# power.net
KiCad netlist of a schematic drawn in Altium Designer
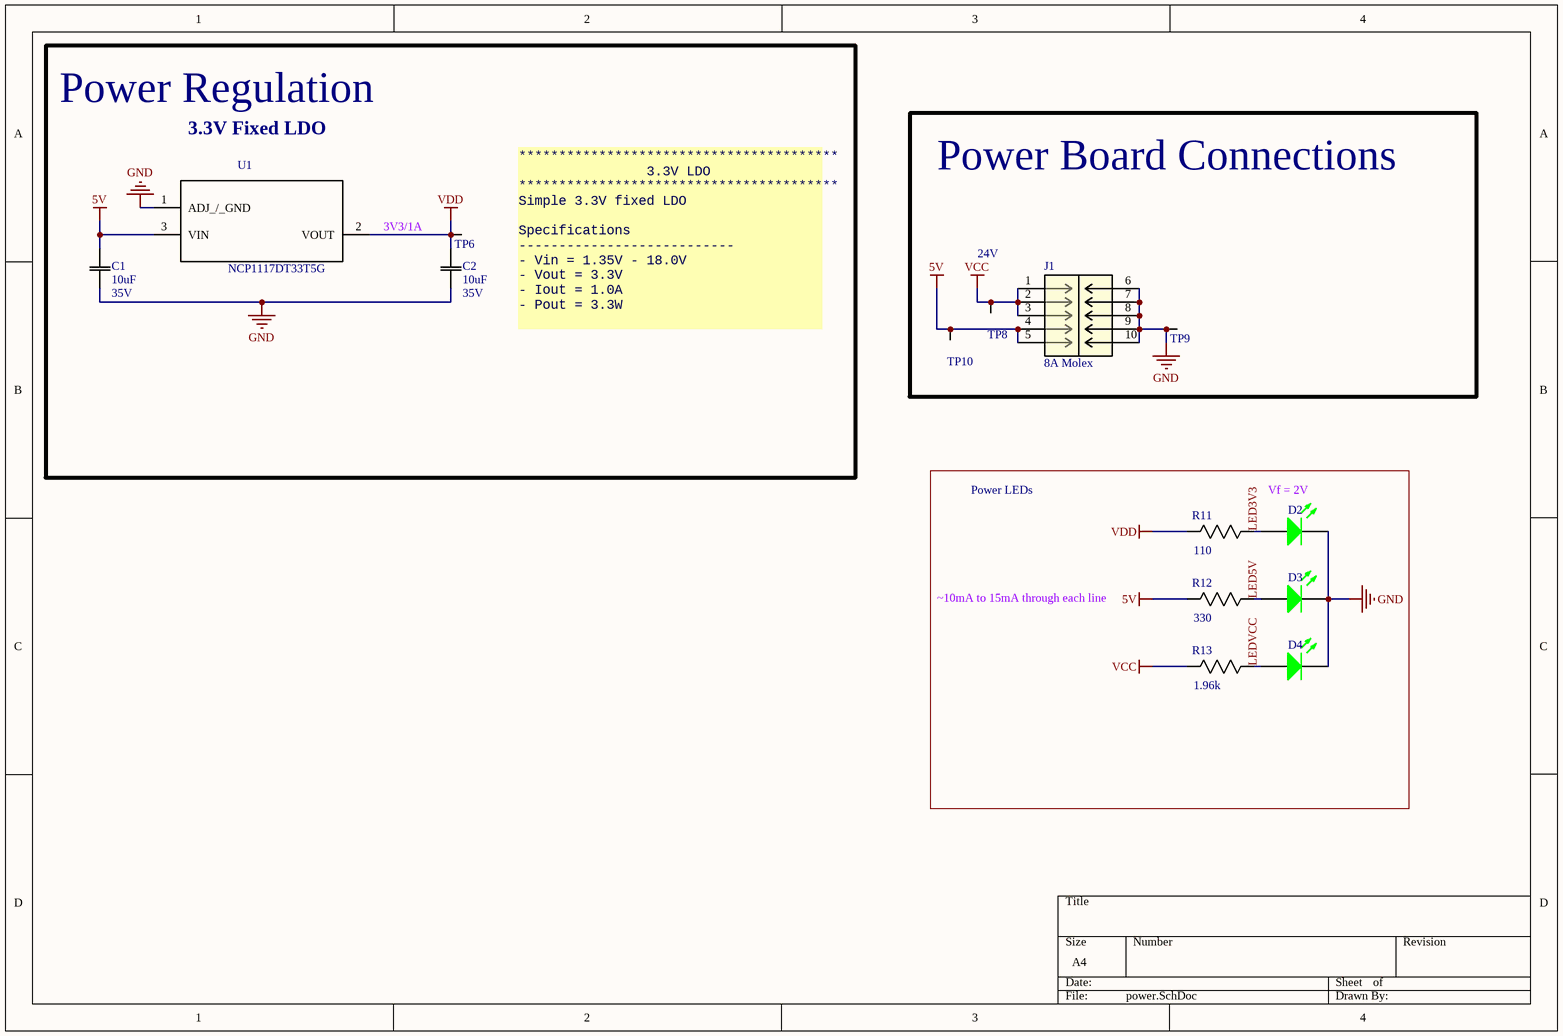
[diagram p0: power.SchDoc]

(export (version "E")
  (design (tool "Eeschema 10.0.6"))
  (components
    (comp (ref "C1")
      (value "10uF")
      (footprint "0805")
      (description "Default Symbol for Capacitors")
      (fields
        (field (name "TOLERANCE") "10%")
        (field (name "RATING") "35V")
        (field (name "PART NUMBER") "CAP 10uF 35V_1")
      )
      (libsource (lib "capacitor_library") (part "CAP_Default"))
    )
    (comp (ref "C2")
      (value "10uF")
      (footprint "0805")
      (description "Default Symbol for Capacitors")
      (fields
        (field (name "TOLERANCE") "10%")
        (field (name "RATING") "35V")
        (field (name "PART NUMBER") "CAP 10uF 35V_1")
      )
      (libsource (lib "capacitor_library") (part "CAP_Default"))
    )
    (comp (ref "D2")
      (value "0603 2V")
      (footprint "0603 - LED")
      (description "LED Uni-Color Green 574nm 2-Pin Chip LED T/R")
      (fields (field (name "PART NUMBER") "LED GREEN SMD 0603"))
      (libsource (lib "Diode_Library") (part "LED GREEN SMD 0603"))
    )
    (comp (ref "D3")
      (value "0603 2V")
      (footprint "0603 - LED")
      (description "LED Uni-Color Green 574nm 2-Pin Chip LED T/R")
      (fields (field (name "PART NUMBER") "LED GREEN SMD 0603"))
      (libsource (lib "Diode_Library") (part "LED GREEN SMD 0603"))
    )
    (comp (ref "D4")
      (value "0603 2V")
      (footprint "0603 - LED")
      (description "LED Uni-Color Green 574nm 2-Pin Chip LED T/R")
      (fields (field (name "PART NUMBER") "LED GREEN SMD 0603"))
      (libsource (lib "Diode_Library") (part "LED GREEN SMD 0603"))
    )
    (comp (ref "J1")
      (value "8A Molex")
      (footprint "MOLEX_0430451012")
      (description "CONN HEADER VERT 10POS 3MM")
      (fields (field (name "PART NUMBER") "CN HDR 10POS MOLEX 0430451012"))
      (libsource (lib "Connector_Library") (part "CN HDR 10POS MOLEX 0430451012"))
    )
    (comp (ref "R11")
      (value "110")
      (footprint "0603")
      (description "Default Resistor Symbol")
      (fields (field (name "TOLERANCE") "1%") (field (name "PART NUMBER") "RES 110.0 1/8W - 1%"))
      (libsource (lib "") (part "RES_DEFAULT_1"))
    )
    (comp (ref "R12")
      (value "330")
      (footprint "0603")
      (description "Default Resistor Symbol")
      (fields (field (name "TOLERANCE") "5%") (field (name "PART NUMBER") "RES 330.0 1/8W - 5%"))
      (libsource (lib "Resistor_Library") (part "RES_DEFAULT"))
    )
    (comp (ref "R13")
      (value "1.96k")
      (footprint "0603")
      (description "Default Resistor Symbol")
      (fields (field (name "TOLERANCE") "1%") (field (name "PART NUMBER") "RES 1.96k 1/8W"))
      (libsource (lib "Resistor_Library") (part "RES_DEFAULT"))
    )
    (comp (ref "TP6")
      (value "VDD")
      (footprint "TP")
      (fields (field (name "PART NUMBER") "Test Point (Via)"))
      (libsource (lib "IC_Library") (part "Test Point (Via)"))
    )
    (comp (ref "TP8")
      (value "VCC")
      (footprint "TP")
      (fields (field (name "PART NUMBER") "Test Point (Via)"))
      (libsource (lib "IC_Library") (part "Test Point (Via)"))
    )
    (comp (ref "TP9")
      (value "GND")
      (footprint "TP")
      (fields (field (name "PART NUMBER") "Test Point (Via)"))
      (libsource (lib "IC_Library") (part "Test Point (Via)"))
    )
    (comp (ref "TP10")
      (value "5V")
      (footprint "TP")
      (fields (field (name "PART NUMBER") "Test Point (Via)"))
      (libsource (lib "IC_Library") (part "Test Point (Via)"))
    )
    (comp (ref "U1")
      (value "NCP1117DT33T5G")
      (footprint "DPAK (TO-252)")
      (description "Linear Voltage Regulator IC Positive Fixed 1 Output 1A DPAK")
      (libsource (lib "IC_Library") (part "NCP1117DT33T5G"))
    )
  )
  (nets
    (net (code "1") (name "/LED3V3") (class "Default")
      (node (ref "D2") (pin "1") (pinfunction "A_1") (pintype "passive"))
      (node (ref "R11") (pin "1") (pinfunction "R1_1") (pintype "passive"))
    )
    (net (code "2") (name "/LED5V") (class "Default")
      (node (ref "D3") (pin "1") (pinfunction "A_1") (pintype "passive"))
      (node (ref "R12") (pin "1") (pinfunction "R1_1") (pintype "passive"))
    )
    (net (code "3") (name "/LEDVCC") (class "Default")
      (node (ref "D4") (pin "1") (pinfunction "A_1") (pintype "passive"))
      (node (ref "R13") (pin "1") (pinfunction "R1_1") (pintype "passive"))
    )
    (net (code "4") (name "5V") (class "Default")
      (node (ref "C1") (pin "2") (pinfunction "C2_2") (pintype "passive"))
      (node (ref "J1") (pin "4") (pinfunction "4_4") (pintype "passive"))
      (node (ref "J1") (pin "5") (pinfunction "5_5") (pintype "passive"))
      (node (ref "R12") (pin "2") (pinfunction "R2_2") (pintype "passive"))
      (node (ref "TP10") (pin "1") (pinfunction "1_1") (pintype "passive"))
      (node (ref "U1") (pin "3") (pinfunction "VIN_3") (pintype "power_in"))
    )
    (net (code "5") (name "GND") (class "Default")
      (node (ref "C1") (pin "1") (pinfunction "C1_1") (pintype "passive"))
      (node (ref "C2") (pin "1") (pinfunction "C1_1") (pintype "passive"))
      (node (ref "D2") (pin "2") (pinfunction "K_2") (pintype "passive"))
      (node (ref "D3") (pin "2") (pinfunction "K_2") (pintype "passive"))
      (node (ref "D4") (pin "2") (pinfunction "K_2") (pintype "passive"))
      (node (ref "J1") (pin "10") (pinfunction "10_10") (pintype "passive"))
      (node (ref "J1") (pin "6") (pinfunction "6_6") (pintype "passive"))
      (node (ref "J1") (pin "7") (pinfunction "7_7") (pintype "passive"))
      (node (ref "J1") (pin "8") (pinfunction "8_8") (pintype "passive"))
      (node (ref "J1") (pin "9") (pinfunction "9_9") (pintype "passive"))
      (node (ref "TP9") (pin "1") (pinfunction "1_1") (pintype "passive"))
      (node (ref "U1") (pin "1") (pinfunction "ADJ_/_GND_1") (pintype "power_in"))
    )
    (net (code "6") (name "VCC") (class "Default")
      (node (ref "J1") (pin "1") (pinfunction "1_1") (pintype "passive"))
      (node (ref "J1") (pin "2") (pinfunction "2_2") (pintype "passive"))
      (node (ref "J1") (pin "3") (pinfunction "3_3") (pintype "passive"))
      (node (ref "R13") (pin "2") (pinfunction "R2_2") (pintype "passive"))
      (node (ref "TP8") (pin "1") (pinfunction "1_1") (pintype "passive"))
    )
    (net (code "7") (name "VDD") (class "Default")
      (node (ref "C2") (pin "2") (pinfunction "C2_2") (pintype "passive"))
      (node (ref "R11") (pin "2") (pinfunction "R2_2") (pintype "passive"))
      (node (ref "TP6") (pin "1") (pinfunction "1_1") (pintype "passive"))
      (node (ref "U1") (pin "2") (pinfunction "VOUT_2") (pintype "power_in"))
    )
  )
)
